# Converter.net
KiCad netlist of a schematic drawn in Altium Designer
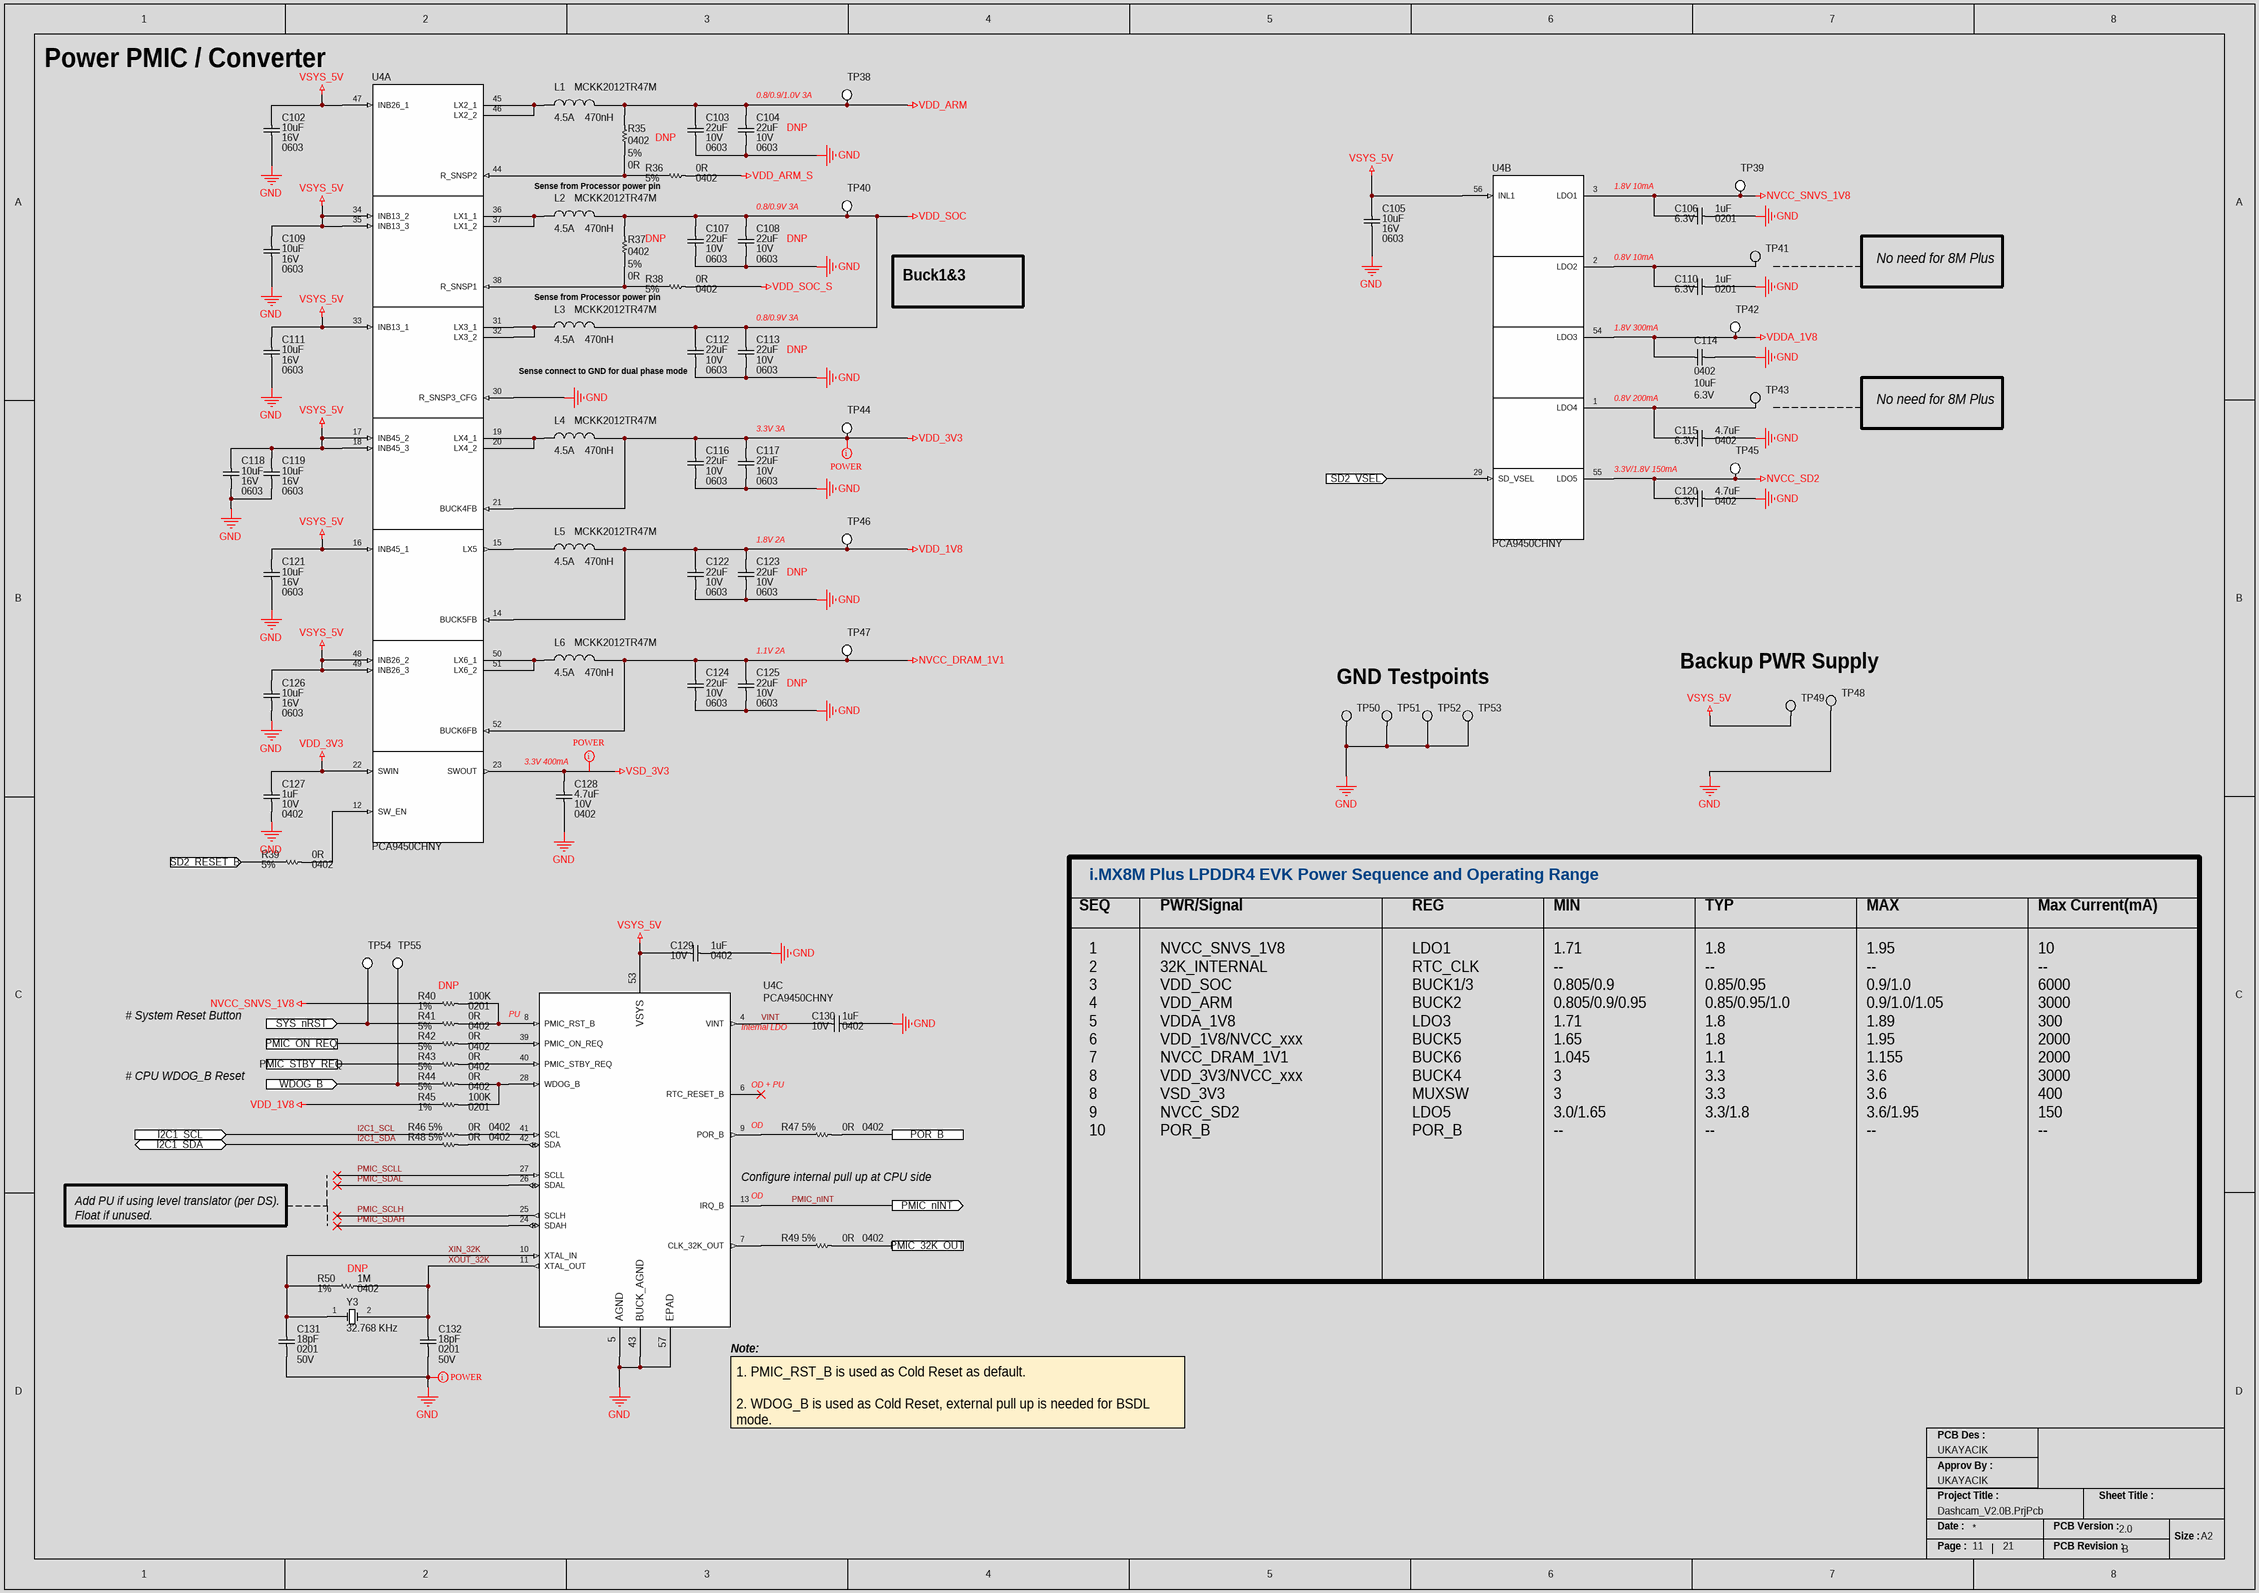
[diagram p0: Converter.SchDoc]

(export (version "E")
  (design (tool "Eeschema 10.0.6"))
  (components
    (comp (ref "C102")
      (value "GRM188R61C106MAALD")
      (footprint "CAP_0603_CAPC1608X08N")
      (description "0603 10 uF 16 V ±20% Tolerance X5R Multilayer Ceramic Chip Capacitor")
      (fields
        (field (name "MANUFACTURER") "Murata")
        (field (name "TOLERANCE") "20%")
        (field (name "VOLTAGE RATING") "16V")
        (field (name "CAPACITANCE") "10uF")
        (field (name "CASE/PACKAGE") "0603")
      )
      (libsource (lib "Electronic Devices_LIB") (part "CAP_10UF_16V_X5R_0603"))
    )
    (comp (ref "C103")
      (value "C1608X5R1A226M080AC")
      (footprint "CAP_0603_CAPC1608X08N")
      (description "Multilayer Ceramic Capacitor, 22 uF, 10 V, ± 20%, X5R, 0603 [1608 Metric]")
      (fields
        (field (name "MANUFACTURER") "TDK")
        (field (name "TOLERANCE") "20%")
        (field (name "CAPACITANCE") "22uF")
        (field (name "VOLTAGE RATING") "10V")
        (field (name "CASE CODE (IMPERIAL)") "0603")
      )
      (libsource (lib "Electronic Devices_LIB") (part "CAP_22UF_10V_X5R_0603"))
    )
    (comp (ref "C104")
      (value "C1608X5R1A226M080AC")
      (footprint "CAP_0603_CAPC1608X08N")
      (description "Multilayer Ceramic Capacitor, 22 uF, 10 V, ± 20%, X5R, 0603 [1608 Metric]")
      (fields
        (field (name "MANUFACTURER") "TDK")
        (field (name "TOLERANCE") "20%")
        (field (name "CAPACITANCE") "22uF")
        (field (name "VOLTAGE RATING") "10V")
        (field (name "CASE CODE (IMPERIAL)") "0603")
      )
      (libsource (lib "Electronic Devices_LIB") (part "CAP_22UF_10V_X5R_0603"))
    )
    (comp (ref "C105")
      (value "GRM188R61C106MAALD")
      (footprint "CAP_0603_CAPC1608X08N")
      (description "0603 10 uF 16 V ±20% Tolerance X5R Multilayer Ceramic Chip Capacitor")
      (fields
        (field (name "MANUFACTURER") "Murata")
        (field (name "TOLERANCE") "20%")
        (field (name "VOLTAGE RATING") "16V")
        (field (name "CAPACITANCE") "10uF")
        (field (name "CASE/PACKAGE") "0603")
      )
      (libsource (lib "Electronic Devices_LIB") (part "CAP_10UF_16V_X5R_0603"))
    )
    (comp (ref "C106")
      (value "02016D105MAT2A")
      (footprint "CAP_0201_CAPC0603X03N")
      (description "0201 1 uF 6.3 V ±20 % Tolerance X5R Surface Mount Multilayer Ceramic Capacitor")
      (fields
        (field (name "MANUFACTURER") "Kyocera AVX")
        (field (name "TOLERANCE") "20%")
        (field (name "VOLTAGE RATING (DC)") "6.3V")
        (field (name "CAPACITANCE") "1uF")
        (field (name "CASE/PACKAGE") "0201")
      )
      (libsource (lib "Electronic Devices_LIB") (part "CAP_1UF_6.3V_X5R_0201"))
    )
    (comp (ref "C107")
      (value "C1608X5R1A226M080AC")
      (footprint "CAP_0603_CAPC1608X08N")
      (description "Multilayer Ceramic Capacitor, 22 uF, 10 V, ± 20%, X5R, 0603 [1608 Metric]")
      (fields
        (field (name "MANUFACTURER") "TDK")
        (field (name "TOLERANCE") "20%")
        (field (name "CAPACITANCE") "22uF")
        (field (name "VOLTAGE RATING") "10V")
        (field (name "CASE CODE (IMPERIAL)") "0603")
      )
      (libsource (lib "Electronic Devices_LIB") (part "CAP_22UF_10V_X5R_0603"))
    )
    (comp (ref "C108")
      (value "C1608X5R1A226M080AC")
      (footprint "CAP_0603_CAPC1608X08N")
      (description "Multilayer Ceramic Capacitor, 22 uF, 10 V, ± 20%, X5R, 0603 [1608 Metric]")
      (fields
        (field (name "MANUFACTURER") "TDK")
        (field (name "TOLERANCE") "20%")
        (field (name "CAPACITANCE") "22uF")
        (field (name "VOLTAGE RATING") "10V")
        (field (name "CASE CODE (IMPERIAL)") "0603")
      )
      (libsource (lib "Electronic Devices_LIB") (part "CAP_22UF_10V_X5R_0603"))
    )
    (comp (ref "C109")
      (value "GRM188R61C106MAALD")
      (footprint "CAP_0603_CAPC1608X08N")
      (description "0603 10 uF 16 V ±20% Tolerance X5R Multilayer Ceramic Chip Capacitor")
      (fields
        (field (name "MANUFACTURER") "Murata")
        (field (name "TOLERANCE") "20%")
        (field (name "VOLTAGE RATING") "16V")
        (field (name "CAPACITANCE") "10uF")
        (field (name "CASE/PACKAGE") "0603")
      )
      (libsource (lib "Electronic Devices_LIB") (part "CAP_10UF_16V_X5R_0603"))
    )
    (comp (ref "C110")
      (value "02016D105MAT2A")
      (footprint "CAP_0201_CAPC0603X03N")
      (description "0201 1 uF 6.3 V ±20 % Tolerance X5R Surface Mount Multilayer Ceramic Capacitor")
      (fields
        (field (name "MANUFACTURER") "Kyocera AVX")
        (field (name "TOLERANCE") "20%")
        (field (name "VOLTAGE RATING (DC)") "6.3V")
        (field (name "CAPACITANCE") "1uF")
        (field (name "CASE/PACKAGE") "0201")
      )
      (libsource (lib "Electronic Devices_LIB") (part "CAP_1UF_6.3V_X5R_0201"))
    )
    (comp (ref "C111")
      (value "GRM188R61C106MAALD")
      (footprint "CAP_0603_CAPC1608X08N")
      (description "0603 10 uF 16 V ±20% Tolerance X5R Multilayer Ceramic Chip Capacitor")
      (fields
        (field (name "MANUFACTURER") "Murata")
        (field (name "TOLERANCE") "20%")
        (field (name "VOLTAGE RATING") "16V")
        (field (name "CAPACITANCE") "10uF")
        (field (name "CASE/PACKAGE") "0603")
      )
      (libsource (lib "Electronic Devices_LIB") (part "CAP_10UF_16V_X5R_0603"))
    )
    (comp (ref "C112")
      (value "C1608X5R1A226M080AC")
      (footprint "CAP_0603_CAPC1608X08N")
      (description "Multilayer Ceramic Capacitor, 22 uF, 10 V, ± 20%, X5R, 0603 [1608 Metric]")
      (fields
        (field (name "MANUFACTURER") "TDK")
        (field (name "TOLERANCE") "20%")
        (field (name "CAPACITANCE") "22uF")
        (field (name "VOLTAGE RATING") "10V")
        (field (name "CASE CODE (IMPERIAL)") "0603")
      )
      (libsource (lib "Electronic Devices_LIB") (part "CAP_22UF_10V_X5R_0603"))
    )
    (comp (ref "C113")
      (value "C1608X5R1A226M080AC")
      (footprint "CAP_0603_CAPC1608X08N")
      (description "Multilayer Ceramic Capacitor, 22 uF, 10 V, ± 20%, X5R, 0603 [1608 Metric]")
      (fields
        (field (name "MANUFACTURER") "TDK")
        (field (name "TOLERANCE") "20%")
        (field (name "CAPACITANCE") "22uF")
        (field (name "VOLTAGE RATING") "10V")
        (field (name "CASE CODE (IMPERIAL)") "0603")
      )
      (libsource (lib "Electronic Devices_LIB") (part "CAP_22UF_10V_X5R_0603"))
    )
    (comp (ref "C114")
      (value "CL05A106MQ5NUNC")
      (footprint "CAP_0402_CAPC1005X05N")
      (description "Cap Ceramic 10uF 6.3V X5R 20% SMD 0402 85C T/R")
      (fields
        (field (name "MANUFACTURER") "Samsung")
        (field (name "TOLERANCE") "20%")
        (field (name "CASE/PACKAGE") "0402")
        (field (name "CAPACITANCE") "10uF")
        (field (name "VOLTAGE RATING") "6.3V")
      )
      (libsource (lib "Electronic Devices_LIB") (part "CAP_10UF_6.3V_X5R_0402"))
    )
    (comp (ref "C115")
      (value "C1005X5R0J475M050BC")
      (footprint "CAP_0402_CAPC1005X05N")
      (description "Multilayer Ceramic Capacitor, 4.7 uF, 6.3 V, ± 20%, X5R, 0402 [1005 Metric]")
      (fields
        (field (name "MANUFACTURER") "TDK")
        (field (name "TOLERANCE") "20%")
        (field (name "CAPACITANCE") "4.7uF")
        (field (name "VOLTAGE RATING") "6.3V")
        (field (name "CASE/PACKAGE") "0402")
      )
      (libsource (lib "Electronic Devices_LIB") (part "CAP_4.7UF_6.3V_X5R_0402"))
    )
    (comp (ref "C116")
      (value "C1608X5R1A226M080AC")
      (footprint "CAP_0603_CAPC1608X08N")
      (description "Multilayer Ceramic Capacitor, 22 uF, 10 V, ± 20%, X5R, 0603 [1608 Metric]")
      (fields
        (field (name "MANUFACTURER") "TDK")
        (field (name "TOLERANCE") "20%")
        (field (name "CAPACITANCE") "22uF")
        (field (name "VOLTAGE RATING") "10V")
        (field (name "CASE CODE (IMPERIAL)") "0603")
      )
      (libsource (lib "Electronic Devices_LIB") (part "CAP_22UF_10V_X5R_0603"))
    )
    (comp (ref "C117")
      (value "C1608X5R1A226M080AC")
      (footprint "CAP_0603_CAPC1608X08N")
      (description "Multilayer Ceramic Capacitor, 22 uF, 10 V, ± 20%, X5R, 0603 [1608 Metric]")
      (fields
        (field (name "MANUFACTURER") "TDK")
        (field (name "TOLERANCE") "20%")
        (field (name "CAPACITANCE") "22uF")
        (field (name "VOLTAGE RATING") "10V")
        (field (name "CASE CODE (IMPERIAL)") "0603")
      )
      (libsource (lib "Electronic Devices_LIB") (part "CAP_22UF_10V_X5R_0603"))
    )
    (comp (ref "C118")
      (value "GRM188R61C106MAALD")
      (footprint "CAP_0603_CAPC1608X08N")
      (description "0603 10 uF 16 V ±20% Tolerance X5R Multilayer Ceramic Chip Capacitor")
      (fields
        (field (name "MANUFACTURER") "Murata")
        (field (name "TOLERANCE") "20%")
        (field (name "VOLTAGE RATING") "16V")
        (field (name "CAPACITANCE") "10uF")
        (field (name "CASE/PACKAGE") "0603")
      )
      (libsource (lib "Electronic Devices_LIB") (part "CAP_10UF_16V_X5R_0603"))
    )
    (comp (ref "C119")
      (value "GRM188R61C106MAALD")
      (footprint "CAP_0603_CAPC1608X08N")
      (description "0603 10 uF 16 V ±20% Tolerance X5R Multilayer Ceramic Chip Capacitor")
      (fields
        (field (name "MANUFACTURER") "Murata")
        (field (name "TOLERANCE") "20%")
        (field (name "VOLTAGE RATING") "16V")
        (field (name "CAPACITANCE") "10uF")
        (field (name "CASE/PACKAGE") "0603")
      )
      (libsource (lib "Electronic Devices_LIB") (part "CAP_10UF_16V_X5R_0603"))
    )
    (comp (ref "C120")
      (value "C1005X5R0J475M050BC")
      (footprint "CAP_0402_CAPC1005X05N")
      (description "Multilayer Ceramic Capacitor, 4.7 uF, 6.3 V, ± 20%, X5R, 0402 [1005 Metric]")
      (fields
        (field (name "MANUFACTURER") "TDK")
        (field (name "TOLERANCE") "20%")
        (field (name "CAPACITANCE") "4.7uF")
        (field (name "VOLTAGE RATING") "6.3V")
        (field (name "CASE/PACKAGE") "0402")
      )
      (libsource (lib "Electronic Devices_LIB") (part "CAP_4.7UF_6.3V_X5R_0402"))
    )
    (comp (ref "C121")
      (value "GRM188R61C106MAALD")
      (footprint "CAP_0603_CAPC1608X08N")
      (description "0603 10 uF 16 V ±20% Tolerance X5R Multilayer Ceramic Chip Capacitor")
      (fields
        (field (name "MANUFACTURER") "Murata")
        (field (name "TOLERANCE") "20%")
        (field (name "VOLTAGE RATING") "16V")
        (field (name "CAPACITANCE") "10uF")
        (field (name "CASE/PACKAGE") "0603")
      )
      (libsource (lib "Electronic Devices_LIB") (part "CAP_10UF_16V_X5R_0603"))
    )
    (comp (ref "C122")
      (value "C1608X5R1A226M080AC")
      (footprint "CAP_0603_CAPC1608X08N")
      (description "Multilayer Ceramic Capacitor, 22 uF, 10 V, ± 20%, X5R, 0603 [1608 Metric]")
      (fields
        (field (name "MANUFACTURER") "TDK")
        (field (name "TOLERANCE") "20%")
        (field (name "CAPACITANCE") "22uF")
        (field (name "VOLTAGE RATING") "10V")
        (field (name "CASE CODE (IMPERIAL)") "0603")
      )
      (libsource (lib "Electronic Devices_LIB") (part "CAP_22UF_10V_X5R_0603"))
    )
    (comp (ref "C123")
      (value "C1608X5R1A226M080AC")
      (footprint "CAP_0603_CAPC1608X08N")
      (description "Multilayer Ceramic Capacitor, 22 uF, 10 V, ± 20%, X5R, 0603 [1608 Metric]")
      (fields
        (field (name "MANUFACTURER") "TDK")
        (field (name "TOLERANCE") "20%")
        (field (name "CAPACITANCE") "22uF")
        (field (name "VOLTAGE RATING") "10V")
        (field (name "CASE CODE (IMPERIAL)") "0603")
      )
      (libsource (lib "Electronic Devices_LIB") (part "CAP_22UF_10V_X5R_0603"))
    )
    (comp (ref "C124")
      (value "C1608X5R1A226M080AC")
      (footprint "CAP_0603_CAPC1608X08N")
      (description "Multilayer Ceramic Capacitor, 22 uF, 10 V, ± 20%, X5R, 0603 [1608 Metric]")
      (fields
        (field (name "MANUFACTURER") "TDK")
        (field (name "TOLERANCE") "20%")
        (field (name "CAPACITANCE") "22uF")
        (field (name "VOLTAGE RATING") "10V")
        (field (name "CASE CODE (IMPERIAL)") "0603")
      )
      (libsource (lib "Electronic Devices_LIB") (part "CAP_22UF_10V_X5R_0603"))
    )
    (comp (ref "C125")
      (value "C1608X5R1A226M080AC")
      (footprint "CAP_0603_CAPC1608X08N")
      (description "Multilayer Ceramic Capacitor, 22 uF, 10 V, ± 20%, X5R, 0603 [1608 Metric]")
      (fields
        (field (name "MANUFACTURER") "TDK")
        (field (name "TOLERANCE") "20%")
        (field (name "CAPACITANCE") "22uF")
        (field (name "VOLTAGE RATING") "10V")
        (field (name "CASE CODE (IMPERIAL)") "0603")
      )
      (libsource (lib "Electronic Devices_LIB") (part "CAP_22UF_10V_X5R_0603"))
    )
    (comp (ref "C126")
      (value "GRM188R61C106MAALD")
      (footprint "CAP_0603_CAPC1608X08N")
      (description "0603 10 uF 16 V ±20% Tolerance X5R Multilayer Ceramic Chip Capacitor")
      (fields
        (field (name "MANUFACTURER") "Murata")
        (field (name "TOLERANCE") "20%")
        (field (name "VOLTAGE RATING") "16V")
        (field (name "CAPACITANCE") "10uF")
        (field (name "CASE/PACKAGE") "0603")
      )
      (libsource (lib "Electronic Devices_LIB") (part "CAP_10UF_16V_X5R_0603"))
    )
    (comp (ref "C127")
      (value "GRM155C81A105KA12D")
      (footprint "CAP_0402_CAPC1005X05N")
      (description "0402 10 V 1 uF ±10% Tolerance X6S Multilayer Ceramic Capacitor")
      (fields
        (field (name "MANUFACTURER") "Murata")
        (field (name "TOLERANCE") "10%")
        (field (name "VOLTAGE RATING") "10V")
        (field (name "CAPACITANCE") "1uF")
        (field (name "CASE/PACKAGE") "0402")
      )
      (libsource (lib "Electronic Devices_LIB") (part "CAP_1UF_10V_X6S_0402"))
    )
    (comp (ref "C128")
      (value "CL05A475KP5NRNC")
      (footprint "CAP_0402_CAPC1005X05N")
      (description "Multilayer Ceramic Capacitor, 4.7 uF, 10 V, ± 10%, X5R, 0402 [1005 Metric]")
      (fields
        (field (name "MANUFACTURER") "Samsung")
        (field (name "TOLERANCE") "10%")
        (field (name "CAPACITANCE") "4.7uF")
        (field (name "VOLTAGE RATING") "10V")
        (field (name "CASE/PACKAGE") "0402")
      )
      (libsource (lib "Electronic Devices_LIB") (part "CAP_4.7UF_10V_X5R_0402"))
    )
    (comp (ref "C129")
      (value "GRM155C81A105KA12D")
      (footprint "CAP_0402_CAPC1005X05N")
      (description "0402 10 V 1 uF ±10% Tolerance X6S Multilayer Ceramic Capacitor")
      (fields
        (field (name "MANUFACTURER") "Murata")
        (field (name "TOLERANCE") "10%")
        (field (name "VOLTAGE RATING") "10V")
        (field (name "CAPACITANCE") "1uF")
        (field (name "CASE/PACKAGE") "0402")
      )
      (libsource (lib "Electronic Devices_LIB") (part "CAP_1UF_10V_X6S_0402"))
    )
    (comp (ref "C130")
      (value "GRM155C81A105KA12D")
      (footprint "CAP_0402_CAPC1005X05N")
      (description "0402 10 V 1 uF ±10% Tolerance X6S Multilayer Ceramic Capacitor")
      (fields
        (field (name "MANUFACTURER") "Murata")
        (field (name "TOLERANCE") "10%")
        (field (name "VOLTAGE RATING") "10V")
        (field (name "CAPACITANCE") "1uF")
        (field (name "CASE/PACKAGE") "0402")
      )
      (libsource (lib "Electronic Devices_LIB") (part "CAP_1UF_10V_X6S_0402"))
    )
    (comp (ref "C131")
      (value "GRM0335C1H180JA01D")
      (footprint "CAP_0201_CAPC0603X03N")
      (description "Multilayer Ceramic Capacitor, 18 pF, 50 V, ± 5%, C0G (NP0), 0201 [0603 Metric]")
      (fields
        (field (name "MANUFACTURER") "Murata")
        (field (name "TOLERANCE") "5%")
        (field (name "CAPACITANCE") "18pF")
        (field (name "VOLTAGE RATING") "50V")
        (field (name "CASE/PACKAGE") "0201")
      )
      (libsource (lib "Electronic Devices_LIB") (part "CAP_18PF_50V_NP0_0201"))
    )
    (comp (ref "C132")
      (value "GRM0335C1H180JA01D")
      (footprint "CAP_0201_CAPC0603X03N")
      (description "Multilayer Ceramic Capacitor, 18 pF, 50 V, ± 5%, C0G (NP0), 0201 [0603 Metric]")
      (fields
        (field (name "MANUFACTURER") "Murata")
        (field (name "TOLERANCE") "5%")
        (field (name "CAPACITANCE") "18pF")
        (field (name "VOLTAGE RATING") "50V")
        (field (name "CASE/PACKAGE") "0201")
      )
      (libsource (lib "Electronic Devices_LIB") (part "CAP_18PF_50V_NP0_0201"))
    )
    (comp (ref "L1")
      (value "MCKK2012TR47M")
      (footprint "IND_0805_INDC2012X10N")
      (description "Inductor Power Chip Multi-Layer 0.47uH 20% 1MHz Metal 3.1A 0.039Ohm DCR 0805 T/R")
      (fields
        (field (name "MANUFACTURER") "Taiyo Yuden")
        (field (name "TOLERANCE") "20%")
        (field (name "CURRENT RATING") "4.5A")
        (field (name "INDUCTANCE") "470nH")
      )
      (libsource (lib "Electronic Devices_LIB") (part "IND_0.47uH_4.5A_MCKK2012TR47M"))
    )
    (comp (ref "L2")
      (value "MCKK2012TR47M")
      (footprint "IND_0805_INDC2012X10N")
      (description "Inductor Power Chip Multi-Layer 0.47uH 20% 1MHz Metal 3.1A 0.039Ohm DCR 0805 T/R")
      (fields
        (field (name "MANUFACTURER") "Taiyo Yuden")
        (field (name "TOLERANCE") "20%")
        (field (name "CURRENT RATING") "4.5A")
        (field (name "INDUCTANCE") "470nH")
      )
      (libsource (lib "Electronic Devices_LIB") (part "IND_0.47uH_4.5A_MCKK2012TR47M"))
    )
    (comp (ref "L3")
      (value "MCKK2012TR47M")
      (footprint "IND_0805_INDC2012X10N")
      (description "Inductor Power Chip Multi-Layer 0.47uH 20% 1MHz Metal 3.1A 0.039Ohm DCR 0805 T/R")
      (fields
        (field (name "MANUFACTURER") "Taiyo Yuden")
        (field (name "TOLERANCE") "20%")
        (field (name "CURRENT RATING") "4.5A")
        (field (name "INDUCTANCE") "470nH")
      )
      (libsource (lib "Electronic Devices_LIB") (part "IND_0.47uH_4.5A_MCKK2012TR47M"))
    )
    (comp (ref "L4")
      (value "MCKK2012TR47M")
      (footprint "IND_0805_INDC2012X10N")
      (description "Inductor Power Chip Multi-Layer 0.47uH 20% 1MHz Metal 3.1A 0.039Ohm DCR 0805 T/R")
      (fields
        (field (name "MANUFACTURER") "Taiyo Yuden")
        (field (name "TOLERANCE") "20%")
        (field (name "CURRENT RATING") "4.5A")
        (field (name "INDUCTANCE") "470nH")
      )
      (libsource (lib "Electronic Devices_LIB") (part "IND_0.47uH_4.5A_MCKK2012TR47M"))
    )
    (comp (ref "L5")
      (value "MCKK2012TR47M")
      (footprint "IND_0805_INDC2012X10N")
      (description "Inductor Power Chip Multi-Layer 0.47uH 20% 1MHz Metal 3.1A 0.039Ohm DCR 0805 T/R")
      (fields
        (field (name "MANUFACTURER") "Taiyo Yuden")
        (field (name "TOLERANCE") "20%")
        (field (name "CURRENT RATING") "4.5A")
        (field (name "INDUCTANCE") "470nH")
      )
      (libsource (lib "Electronic Devices_LIB") (part "IND_0.47uH_4.5A_MCKK2012TR47M"))
    )
    (comp (ref "L6")
      (value "MCKK2012TR47M")
      (footprint "IND_0805_INDC2012X10N")
      (description "Inductor Power Chip Multi-Layer 0.47uH 20% 1MHz Metal 3.1A 0.039Ohm DCR 0805 T/R")
      (fields
        (field (name "MANUFACTURER") "Taiyo Yuden")
        (field (name "TOLERANCE") "20%")
        (field (name "CURRENT RATING") "4.5A")
        (field (name "INDUCTANCE") "470nH")
      )
      (libsource (lib "Electronic Devices_LIB") (part "IND_0.47uH_4.5A_MCKK2012TR47M"))
    )
    (comp (ref "R35")
      (value "ERJ-2GE0R00X")
      (footprint "RES_0402_RESC1005X04N")
      (description "SMD Chip Resistor, Jumper, 0 ohm, 100 mW, 0402 [1005 Metric], Thick Film, General Purpose")
      (fields
        (field (name "MANUFACTURER") "Panasonic")
        (field (name "CASE CODE (IMPERIAL)") "0402")
        (field (name "TOLERANCE") "5%")
        (field (name "RESISTANCE") "0R")
      )
      (libsource (lib "Electronic Devices_LIB") (part "RES_0R_5%_100mW_0402"))
    )
    (comp (ref "R36")
      (value "ERJ-2GE0R00X")
      (footprint "RES_0402_RESC1005X04N")
      (description "SMD Chip Resistor, Jumper, 0 ohm, 100 mW, 0402 [1005 Metric], Thick Film, General Purpose")
      (fields
        (field (name "MANUFACTURER") "Panasonic")
        (field (name "CASE CODE (IMPERIAL)") "0402")
        (field (name "TOLERANCE") "5%")
        (field (name "RESISTANCE") "0R")
      )
      (libsource (lib "Electronic Devices_LIB") (part "RES_0R_5%_100mW_0402"))
    )
    (comp (ref "R37")
      (value "ERJ-2GE0R00X")
      (footprint "RES_0402_RESC1005X04N")
      (description "SMD Chip Resistor, Jumper, 0 ohm, 100 mW, 0402 [1005 Metric], Thick Film, General Purpose")
      (fields
        (field (name "MANUFACTURER") "Panasonic")
        (field (name "CASE CODE (IMPERIAL)") "0402")
        (field (name "TOLERANCE") "5%")
        (field (name "RESISTANCE") "0R")
      )
      (libsource (lib "Electronic Devices_LIB") (part "RES_0R_5%_100mW_0402"))
    )
    (comp (ref "R38")
      (value "ERJ-2GE0R00X")
      (footprint "RES_0402_RESC1005X04N")
      (description "SMD Chip Resistor, Jumper, 0 ohm, 100 mW, 0402 [1005 Metric], Thick Film, General Purpose")
      (fields
        (field (name "MANUFACTURER") "Panasonic")
        (field (name "CASE CODE (IMPERIAL)") "0402")
        (field (name "TOLERANCE") "5%")
        (field (name "RESISTANCE") "0R")
      )
      (libsource (lib "Electronic Devices_LIB") (part "RES_0R_5%_100mW_0402"))
    )
    (comp (ref "R39")
      (value "ERJ-2GE0R00X")
      (footprint "RES_0402_RESC1005X04N")
      (description "SMD Chip Resistor, Jumper, 0 ohm, 100 mW, 0402 [1005 Metric], Thick Film, General Purpose")
      (fields
        (field (name "MANUFACTURER") "Panasonic")
        (field (name "CASE CODE (IMPERIAL)") "0402")
        (field (name "TOLERANCE") "5%")
        (field (name "RESISTANCE") "0R")
      )
      (libsource (lib "Electronic Devices_LIB") (part "RES_0R_5%_100mW_0402"))
    )
    (comp (ref "R40")
      (value "RC0201FR-07100KL")
      (footprint "RES_0201_RESC0603X02N")
      (description "SMD Chip Resistor, 100 kOhm, ± 1%, 50 mW, 0201 [0603 Metric], Thick Film, General Purpose")
      (fields
        (field (name "MANUFACTURER") "Yageo")
        (field (name "RESISTANCE") "100K")
        (field (name "TOLERANCE") "1%")
        (field (name "CASE/PACKAGE") "0201")
      )
      (libsource (lib "Electronic Devices_LIB") (part "RES_100K_1%_50mW_0201"))
    )
    (comp (ref "R41")
      (value "ERJ-2GE0R00X")
      (footprint "RES_0402_RESC1005X04N")
      (description "SMD Chip Resistor, Jumper, 0 ohm, 100 mW, 0402 [1005 Metric], Thick Film, General Purpose")
      (fields
        (field (name "MANUFACTURER") "Panasonic")
        (field (name "CASE CODE (IMPERIAL)") "0402")
        (field (name "TOLERANCE") "5%")
        (field (name "RESISTANCE") "0R")
      )
      (libsource (lib "Electronic Devices_LIB") (part "RES_0R_5%_100mW_0402"))
    )
    (comp (ref "R42")
      (value "ERJ-2GE0R00X")
      (footprint "RES_0402_RESC1005X04N")
      (description "SMD Chip Resistor, Jumper, 0 ohm, 100 mW, 0402 [1005 Metric], Thick Film, General Purpose")
      (fields
        (field (name "MANUFACTURER") "Panasonic")
        (field (name "CASE CODE (IMPERIAL)") "0402")
        (field (name "TOLERANCE") "5%")
        (field (name "RESISTANCE") "0R")
      )
      (libsource (lib "Electronic Devices_LIB") (part "RES_0R_5%_100mW_0402"))
    )
    (comp (ref "R43")
      (value "ERJ-2GE0R00X")
      (footprint "RES_0402_RESC1005X04N")
      (description "SMD Chip Resistor, Jumper, 0 ohm, 100 mW, 0402 [1005 Metric], Thick Film, General Purpose")
      (fields
        (field (name "MANUFACTURER") "Panasonic")
        (field (name "CASE CODE (IMPERIAL)") "0402")
        (field (name "TOLERANCE") "5%")
        (field (name "RESISTANCE") "0R")
      )
      (libsource (lib "Electronic Devices_LIB") (part "RES_0R_5%_100mW_0402"))
    )
    (comp (ref "R44")
      (value "ERJ-2GE0R00X")
      (footprint "RES_0402_RESC1005X04N")
      (description "SMD Chip Resistor, Jumper, 0 ohm, 100 mW, 0402 [1005 Metric], Thick Film, General Purpose")
      (fields
        (field (name "MANUFACTURER") "Panasonic")
        (field (name "CASE CODE (IMPERIAL)") "0402")
        (field (name "TOLERANCE") "5%")
        (field (name "RESISTANCE") "0R")
      )
      (libsource (lib "Electronic Devices_LIB") (part "RES_0R_5%_100mW_0402"))
    )
    (comp (ref "R45")
      (value "RC0201FR-07100KL")
      (footprint "RES_0201_RESC0603X02N")
      (description "SMD Chip Resistor, 100 kOhm, ± 1%, 50 mW, 0201 [0603 Metric], Thick Film, General Purpose")
      (fields
        (field (name "MANUFACTURER") "Yageo")
        (field (name "RESISTANCE") "100K")
        (field (name "TOLERANCE") "1%")
        (field (name "CASE/PACKAGE") "0201")
      )
      (libsource (lib "Electronic Devices_LIB") (part "RES_100K_1%_50mW_0201"))
    )
    (comp (ref "R46")
      (value "ERJ-2GE0R00X")
      (footprint "RES_0402_RESC1005X04N")
      (description "SMD Chip Resistor, Jumper, 0 ohm, 100 mW, 0402 [1005 Metric], Thick Film, General Purpose")
      (fields
        (field (name "MANUFACTURER") "Panasonic")
        (field (name "CASE CODE (IMPERIAL)") "0402")
        (field (name "TOLERANCE") "5%")
        (field (name "RESISTANCE") "0R")
      )
      (libsource (lib "Electronic Devices_LIB") (part "RES_0R_5%_100mW_0402"))
    )
    (comp (ref "R47")
      (value "ERJ-2GE0R00X")
      (footprint "RES_0402_RESC1005X04N")
      (description "SMD Chip Resistor, Jumper, 0 ohm, 100 mW, 0402 [1005 Metric], Thick Film, General Purpose")
      (fields
        (field (name "MANUFACTURER") "Panasonic")
        (field (name "CASE CODE (IMPERIAL)") "0402")
        (field (name "TOLERANCE") "5%")
        (field (name "RESISTANCE") "0R")
      )
      (libsource (lib "Electronic Devices_LIB") (part "RES_0R_5%_100mW_0402"))
    )
    (comp (ref "R48")
      (value "ERJ-2GE0R00X")
      (footprint "RES_0402_RESC1005X04N")
      (description "SMD Chip Resistor, Jumper, 0 ohm, 100 mW, 0402 [1005 Metric], Thick Film, General Purpose")
      (fields
        (field (name "MANUFACTURER") "Panasonic")
        (field (name "CASE CODE (IMPERIAL)") "0402")
        (field (name "TOLERANCE") "5%")
        (field (name "RESISTANCE") "0R")
      )
      (libsource (lib "Electronic Devices_LIB") (part "RES_0R_5%_100mW_0402"))
    )
    (comp (ref "R49")
      (value "ERJ-2GE0R00X")
      (footprint "RES_0402_RESC1005X04N")
      (description "SMD Chip Resistor, Jumper, 0 ohm, 100 mW, 0402 [1005 Metric], Thick Film, General Purpose")
      (fields
        (field (name "MANUFACTURER") "Panasonic")
        (field (name "CASE CODE (IMPERIAL)") "0402")
        (field (name "TOLERANCE") "5%")
        (field (name "RESISTANCE") "0R")
      )
      (libsource (lib "Electronic Devices_LIB") (part "RES_0R_5%_100mW_0402"))
    )
    (comp (ref "R50")
      (value "CR0402-FX-1004GLF")
      (footprint "RES_0402_RESC1005X04N")
      (description "Res Thick Film 0402 1M Ohm 1% 1/16W ±100ppm/°C Molded SMD SMD Paper Tape on Plastic Reel")
      (fields
        (field (name "MANUFACTURER") "Bourns")
        (field (name "RESISTANCE") "1M")
        (field (name "TOLERANCE") "1%")
        (field (name "CASE/PACKAGE") "0402")
      )
      (libsource (lib "Electronic Devices_LIB") (part "RES_1M_1%_63mW_0402"))
    )
    (comp (ref "TP38")
      (value "NO COMPONENT")
      (footprint "TP_PAD_0.8MM_SMD_ROUND")
      (description "Test Point, SMD pad, round, 1.5mm, 1.6mm, 3mm diameter")
      (libsource (lib "Electronic Devices_LIB") (part "TP_PAD_SMD_Round"))
    )
    (comp (ref "TP39")
      (value "NO COMPONENT")
      (footprint "TP_PAD_0.8MM_SMD_ROUND")
      (description "Test Point, SMD pad, round, 1.5mm, 1.6mm, 3mm diameter")
      (libsource (lib "Electronic Devices_LIB") (part "TP_PAD_SMD_Round"))
    )
    (comp (ref "TP40")
      (value "NO COMPONENT")
      (footprint "TP_PAD_0.8MM_SMD_ROUND")
      (description "Test Point, SMD pad, round, 1.5mm, 1.6mm, 3mm diameter")
      (libsource (lib "Electronic Devices_LIB") (part "TP_PAD_SMD_Round"))
    )
    (comp (ref "TP41")
      (value "NO COMPONENT")
      (footprint "TP_PAD_0.5MM_SMD_ROUND")
      (description "Test Point, SMD pad, round, 1.5mm, 1.6mm, 3mm diameter")
      (libsource (lib "Electronic Devices_LIB") (part "TP_PAD_SMD_SMALL"))
    )
    (comp (ref "TP42")
      (value "NO COMPONENT")
      (footprint "TP_PAD_0.8MM_SMD_ROUND")
      (description "Test Point, SMD pad, round, 1.5mm, 1.6mm, 3mm diameter")
      (libsource (lib "Electronic Devices_LIB") (part "TP_PAD_SMD_Round"))
    )
    (comp (ref "TP43")
      (value "NO COMPONENT")
      (footprint "TP_PAD_0.5MM_SMD_ROUND")
      (description "Test Point, SMD pad, round, 1.5mm, 1.6mm, 3mm diameter")
      (libsource (lib "Electronic Devices_LIB") (part "TP_PAD_SMD_SMALL"))
    )
    (comp (ref "TP44")
      (value "NO COMPONENT")
      (footprint "TP_PAD_0.8MM_SMD_ROUND")
      (description "Test Point, SMD pad, round, 1.5mm, 1.6mm, 3mm diameter")
      (libsource (lib "Electronic Devices_LIB") (part "TP_PAD_SMD_Round"))
    )
    (comp (ref "TP45")
      (value "NO COMPONENT")
      (footprint "TP_PAD_0.8MM_SMD_ROUND")
      (description "Test Point, SMD pad, round, 1.5mm, 1.6mm, 3mm diameter")
      (libsource (lib "Electronic Devices_LIB") (part "TP_PAD_SMD_Round"))
    )
    (comp (ref "TP46")
      (value "NO COMPONENT")
      (footprint "TP_PAD_0.8MM_SMD_ROUND")
      (description "Test Point, SMD pad, round, 1.5mm, 1.6mm, 3mm diameter")
      (libsource (lib "Electronic Devices_LIB") (part "TP_PAD_SMD_Round"))
    )
    (comp (ref "TP47")
      (value "NO COMPONENT")
      (footprint "TP_PAD_0.8MM_SMD_ROUND")
      (description "Test Point, SMD pad, round, 1.5mm, 1.6mm, 3mm diameter")
      (libsource (lib "Electronic Devices_LIB") (part "TP_PAD_SMD_Round"))
    )
    (comp (ref "TP48")
      (value "NO COMPONENT")
      (footprint "TP_PAD_0.5MM_SMD_ROUND")
      (description "Test Point, SMD pad, round, 1.5mm, 1.6mm, 3mm diameter")
      (libsource (lib "Electronic Devices_LIB") (part "TP_PAD_SMD_SMALL"))
    )
    (comp (ref "TP49")
      (value "NO COMPONENT")
      (footprint "TP_PAD_0.5MM_SMD_ROUND")
      (description "Test Point, SMD pad, round, 1.5mm, 1.6mm, 3mm diameter")
      (libsource (lib "Electronic Devices_LIB") (part "TP_PAD_SMD_SMALL"))
    )
    (comp (ref "TP50")
      (value "NO COMPONENT")
      (footprint "TP_PAD_0.5MM_SMD_ROUND")
      (description "Test Point, SMD pad, round, 1.5mm, 1.6mm, 3mm diameter")
      (libsource (lib "Electronic Devices_LIB") (part "TP_PAD_SMD_SMALL"))
    )
    (comp (ref "TP51")
      (value "NO COMPONENT")
      (footprint "TP_PAD_0.5MM_SMD_ROUND")
      (description "Test Point, SMD pad, round, 1.5mm, 1.6mm, 3mm diameter")
      (libsource (lib "Electronic Devices_LIB") (part "TP_PAD_SMD_SMALL"))
    )
    (comp (ref "TP52")
      (value "NO COMPONENT")
      (footprint "TP_PAD_0.5MM_SMD_ROUND")
      (description "Test Point, SMD pad, round, 1.5mm, 1.6mm, 3mm diameter")
      (libsource (lib "Electronic Devices_LIB") (part "TP_PAD_SMD_SMALL"))
    )
    (comp (ref "TP53")
      (value "NO COMPONENT")
      (footprint "TP_PAD_0.5MM_SMD_ROUND")
      (description "Test Point, SMD pad, round, 1.5mm, 1.6mm, 3mm diameter")
      (libsource (lib "Electronic Devices_LIB") (part "TP_PAD_SMD_SMALL"))
    )
    (comp (ref "TP54")
      (value "NO COMPONENT")
      (footprint "TP_PAD_0.8MM_SMD_ROUND")
      (description "Test Point, SMD pad, round, 1.5mm, 1.6mm, 3mm diameter")
      (libsource (lib "Electronic Devices_LIB") (part "TP_PAD_SMD_Round"))
    )
    (comp (ref "TP55")
      (value "NO COMPONENT")
      (footprint "TP_PAD_0.8MM_SMD_ROUND")
      (description "Test Point, SMD pad, round, 1.5mm, 1.6mm, 3mm diameter")
      (libsource (lib "Electronic Devices_LIB") (part "TP_PAD_SMD_Round"))
    )
    (comp (ref "U4")
      (value "PCA9450CHNY")
      (footprint "IC_PMIC_QFN40P800X800X100-57N-D")
      (description "SAMPLE FPN ONLY - Power Management Specialized - PMIC PMIC for i.MX8M Plus(865S)")
      (fields (field (name "MANUFACTURER") "NXP Semiconductors"))
      (libsource (lib "Electronic Devices_LIB") (part "IC_PMIC_8MPLUS_PCA9450CHNY"))
    )
    (comp (ref "Y3")
      (value "ABS07-32.768KHZ-T")
      (footprint "CRYSTAL_ABS07-32.768KHZ-T")
      (description "Crystal 0.032768MHz ±20ppm (Tol) 12.5pF Flexural 70000Ohm 2-Pin CSMD T/R")
      (fields
        (field (name "MANUFACTURER") "Abracon")
        (field (name "TOLERANCE") "20ppm")
        (field (name "OPERATING FREQUENCY") "32.768 KHz")
      )
      (libsource (lib "Electronic Devices_LIB") (part "CRYSTAL_ABRACON_32.768KHz_ABS07-32.768KHZ-T"))
    )
  )
  (nets
    (net (code "1") (name "/I2C1_SCL") (class "Default")
      (node (ref "R46") (pin "1") (pinfunction "1_1") (pintype "passive"))
    )
    (net (code "2") (name "/I2C1_SDA") (class "Default")
      (node (ref "R48") (pin "1") (pinfunction "1_1") (pintype "passive"))
    )
    (net (code "3") (name "/PMIC_32K_OUT") (class "Default")
      (node (ref "R49") (pin "2") (pinfunction "2_2") (pintype "passive"))
    )
    (net (code "4") (name "/PMIC_ON_REQ") (class "Default")
      (node (ref "R42") (pin "1") (pinfunction "1_1") (pintype "passive"))
    )
    (net (code "5") (name "/PMIC_SCLH") (class "Default")
      (node (ref "U4") (pin "25") (pinfunction "SCLH_25") (pintype "output+no_connect"))
    )
    (net (code "6") (name "/PMIC_SCLL") (class "Default")
      (node (ref "U4") (pin "27") (pinfunction "SCLL_27") (pintype "input+no_connect"))
    )
    (net (code "7") (name "/PMIC_SDAH") (class "Default")
      (node (ref "U4") (pin "24") (pinfunction "SDAH_24") (pintype "bidirectional+no_connect"))
    )
    (net (code "8") (name "/PMIC_SDAL") (class "Default")
      (node (ref "U4") (pin "26") (pinfunction "SDAL_26") (pintype "bidirectional+no_connect"))
    )
    (net (code "9") (name "/PMIC_STBY_REQ") (class "Default")
      (node (ref "R43") (pin "1") (pinfunction "1_1") (pintype "passive"))
    )
    (net (code "10") (name "/PMIC_nINT") (class "Default")
      (node (ref "U4") (pin "13") (pinfunction "IRQ_B_13") (pintype "open_collector"))
    )
    (net (code "11") (name "/POR_B") (class "Default")
      (node (ref "R47") (pin "2") (pinfunction "2_2") (pintype "passive"))
    )
    (net (code "12") (name "/SD2_RESET_B") (class "Default")
      (node (ref "R39") (pin "1") (pinfunction "1_1") (pintype "passive"))
    )
    (net (code "13") (name "/SD2_VSEL") (class "Default")
      (node (ref "U4") (pin "29") (pinfunction "SD_VSEL_29") (pintype "input"))
    )
    (net (code "14") (name "/SYS_nRST") (class "Default")
      (node (ref "R41") (pin "1") (pinfunction "1_1") (pintype "passive"))
      (node (ref "TP54") (pin "1") (pinfunction "1_1") (pintype "passive"))
    )
    (net (code "15") (name "/VINT") (class "Default")
      (node (ref "C130") (pin "2") (pinfunction "2_2") (pintype "passive"))
      (node (ref "U4") (pin "4") (pinfunction "VINT_4") (pintype "output"))
    )
    (net (code "16") (name "/WDOG_B") (class "Default")
      (node (ref "R44") (pin "1") (pinfunction "1_1") (pintype "passive"))
      (node (ref "TP55") (pin "1") (pinfunction "1_1") (pintype "passive"))
    )
    (net (code "17") (name "/XIN_32K") (class "Default")
      (node (ref "C131") (pin "2") (pinfunction "2_2") (pintype "passive"))
      (node (ref "R50") (pin "1") (pinfunction "1_1") (pintype "passive"))
      (node (ref "U4") (pin "10") (pinfunction "XTAL_IN_10") (pintype "input"))
      (node (ref "Y3") (pin "1") (pinfunction "OSC1_1") (pintype "passive"))
    )
    (net (code "18") (name "/XOUT_32K") (class "Default")
      (node (ref "C132") (pin "2") (pinfunction "2_2") (pintype "passive"))
      (node (ref "R50") (pin "2") (pinfunction "2_2") (pintype "passive"))
      (node (ref "U4") (pin "11") (pinfunction "XTAL_OUT_11") (pintype "output"))
      (node (ref "Y3") (pin "2") (pinfunction "OSC2_2") (pintype "passive"))
    )
    (net (code "19") (name "GND") (class "Default")
      (node (ref "C102") (pin "1") (pinfunction "1_1") (pintype "passive"))
      (node (ref "C103") (pin "1") (pinfunction "1_1") (pintype "passive"))
      (node (ref "C104") (pin "1") (pinfunction "1_1") (pintype "passive"))
      (node (ref "C105") (pin "1") (pinfunction "1_1") (pintype "passive"))
      (node (ref "C106") (pin "2") (pinfunction "2_2") (pintype "passive"))
      (node (ref "C107") (pin "1") (pinfunction "1_1") (pintype "passive"))
      (node (ref "C108") (pin "1") (pinfunction "1_1") (pintype "passive"))
      (node (ref "C109") (pin "1") (pinfunction "1_1") (pintype "passive"))
      (node (ref "C110") (pin "2") (pinfunction "2_2") (pintype "passive"))
      (node (ref "C111") (pin "1") (pinfunction "1_1") (pintype "passive"))
      (node (ref "C112") (pin "1") (pinfunction "1_1") (pintype "passive"))
      (node (ref "C113") (pin "1") (pinfunction "1_1") (pintype "passive"))
      (node (ref "C114") (pin "1") (pinfunction "1_1") (pintype "passive"))
      (node (ref "C115") (pin "2") (pinfunction "2_2") (pintype "passive"))
      (node (ref "C116") (pin "1") (pinfunction "1_1") (pintype "passive"))
      (node (ref "C117") (pin "1") (pinfunction "1_1") (pintype "passive"))
      (node (ref "C118") (pin "1") (pinfunction "1_1") (pintype "passive"))
      (node (ref "C119") (pin "1") (pinfunction "1_1") (pintype "passive"))
      (node (ref "C120") (pin "2") (pinfunction "2_2") (pintype "passive"))
      (node (ref "C121") (pin "1") (pinfunction "1_1") (pintype "passive"))
      (node (ref "C122") (pin "1") (pinfunction "1_1") (pintype "passive"))
      (node (ref "C123") (pin "1") (pinfunction "1_1") (pintype "passive"))
      (node (ref "C124") (pin "1") (pinfunction "1_1") (pintype "passive"))
      (node (ref "C125") (pin "1") (pinfunction "1_1") (pintype "passive"))
      (node (ref "C126") (pin "1") (pinfunction "1_1") (pintype "passive"))
      (node (ref "C127") (pin "1") (pinfunction "1_1") (pintype "passive"))
      (node (ref "C128") (pin "1") (pinfunction "1_1") (pintype "passive"))
      (node (ref "C129") (pin "1") (pinfunction "1_1") (pintype "passive"))
      (node (ref "C130") (pin "1") (pinfunction "1_1") (pintype "passive"))
      (node (ref "C131") (pin "1") (pinfunction "1_1") (pintype "passive"))
      (node (ref "C132") (pin "1") (pinfunction "1_1") (pintype "passive"))
      (node (ref "TP48") (pin "1") (pinfunction "1_1") (pintype "passive"))
      (node (ref "TP50") (pin "1") (pinfunction "1_1") (pintype "passive"))
      (node (ref "TP51") (pin "1") (pinfunction "1_1") (pintype "passive"))
      (node (ref "TP52") (pin "1") (pinfunction "1_1") (pintype "passive"))
      (node (ref "TP53") (pin "1") (pinfunction "1_1") (pintype "passive"))
      (node (ref "U4") (pin "30") (pinfunction "R_SNSP3_CFG_30") (pintype "input"))
      (node (ref "U4") (pin "43") (pinfunction "BUCK_AGND_43") (pintype "power_in"))
      (node (ref "U4") (pin "5") (pinfunction "AGND_5") (pintype "power_in"))
      (node (ref "U4") (pin "57") (pinfunction "EPAD_57") (pintype "power_in"))
    )
    (net (code "20") (name "NVCC_DRAM_1V1") (class "Default")
      (node (ref "C124") (pin "2") (pinfunction "2_2") (pintype "passive"))
      (node (ref "C125") (pin "2") (pinfunction "2_2") (pintype "passive"))
      (node (ref "L6") (pin "2") (pinfunction "2_2") (pintype "passive"))
      (node (ref "TP47") (pin "1") (pinfunction "1_1") (pintype "passive"))
      (node (ref "U4") (pin "52") (pinfunction "BUCK6FB_52") (pintype "input"))
    )
    (net (code "21") (name "NVCC_SD2") (class "Default")
      (node (ref "C120") (pin "1") (pinfunction "1_1") (pintype "passive"))
      (node (ref "TP45") (pin "1") (pinfunction "1_1") (pintype "passive"))
      (node (ref "U4") (pin "55") (pinfunction "LDO5_55") (pintype "passive"))
    )
    (net (code "22") (name "NVCC_SNVS_1V8") (class "Default")
      (node (ref "C106") (pin "1") (pinfunction "1_1") (pintype "passive"))
      (node (ref "R40") (pin "1") (pinfunction "1_1") (pintype "passive"))
      (node (ref "TP39") (pin "1") (pinfunction "1_1") (pintype "passive"))
      (node (ref "U4") (pin "3") (pinfunction "LDO1_3") (pintype "passive"))
    )
    (net (code "23") (name "Net-(U4A-LX1_1)") (class "Default")
      (node (ref "L2") (pin "1") (pinfunction "1_1") (pintype "passive"))
      (node (ref "U4") (pin "36") (pinfunction "LX1_1_36") (pintype "passive"))
      (node (ref "U4") (pin "37") (pinfunction "LX1_2_37") (pintype "passive"))
    )
    (net (code "24") (name "Net-(U4A-LX2_1)") (class "Default")
      (node (ref "L1") (pin "1") (pinfunction "1_1") (pintype "passive"))
      (node (ref "U4") (pin "45") (pinfunction "LX2_1_45") (pintype "passive"))
      (node (ref "U4") (pin "46") (pinfunction "LX2_2_46") (pintype "passive"))
    )
    (net (code "25") (name "Net-(U4A-LX3_1)") (class "Default")
      (node (ref "L3") (pin "1") (pinfunction "1_1") (pintype "passive"))
      (node (ref "U4") (pin "31") (pinfunction "LX3_1_31") (pintype "passive"))
      (node (ref "U4") (pin "32") (pinfunction "LX3_2_32") (pintype "passive"))
    )
    (net (code "26") (name "Net-(U4A-LX4_1)") (class "Default")
      (node (ref "L4") (pin "1") (pinfunction "1_1") (pintype "passive"))
      (node (ref "U4") (pin "19") (pinfunction "LX4_1_19") (pintype "passive"))
      (node (ref "U4") (pin "20") (pinfunction "LX4_2_20") (pintype "passive"))
    )
    (net (code "27") (name "Net-(U4A-LX5)") (class "Default")
      (node (ref "L5") (pin "1") (pinfunction "1_1") (pintype "passive"))
      (node (ref "U4") (pin "15") (pinfunction "LX5_15") (pintype "output"))
    )
    (net (code "28") (name "Net-(U4A-LX6_1)") (class "Default")
      (node (ref "L6") (pin "1") (pinfunction "1_1") (pintype "passive"))
      (node (ref "U4") (pin "50") (pinfunction "LX6_1_50") (pintype "passive"))
      (node (ref "U4") (pin "51") (pinfunction "LX6_2_51") (pintype "passive"))
    )
    (net (code "29") (name "Net-(U4A-R_SNSP1)") (class "Default")
      (node (ref "R37") (pin "1") (pinfunction "1_1") (pintype "passive"))
      (node (ref "R38") (pin "1") (pinfunction "1_1") (pintype "passive"))
      (node (ref "U4") (pin "38") (pinfunction "R_SNSP1_38") (pintype "input"))
    )
    (net (code "30") (name "Net-(U4A-R_SNSP2)") (class "Default")
      (node (ref "R35") (pin "1") (pinfunction "1_1") (pintype "passive"))
      (node (ref "R36") (pin "1") (pinfunction "1_1") (pintype "passive"))
      (node (ref "U4") (pin "44") (pinfunction "R_SNSP2_44") (pintype "input"))
    )
    (net (code "31") (name "Net-(U4A-SW_EN)") (class "Default")
      (node (ref "R39") (pin "2") (pinfunction "2_2") (pintype "passive"))
      (node (ref "U4") (pin "12") (pinfunction "SW_EN_12") (pintype "input"))
    )
    (net (code "32") (name "Net-(U4B-LDO2)") (class "Default")
      (node (ref "C110") (pin "1") (pinfunction "1_1") (pintype "passive"))
      (node (ref "TP41") (pin "1") (pinfunction "1_1") (pintype "passive"))
      (node (ref "U4") (pin "2") (pinfunction "LDO2_2") (pintype "passive"))
    )
    (net (code "33") (name "Net-(U4B-LDO4)") (class "Default")
      (node (ref "C115") (pin "1") (pinfunction "1_1") (pintype "passive"))
      (node (ref "TP43") (pin "1") (pinfunction "1_1") (pintype "passive"))
      (node (ref "U4") (pin "1") (pinfunction "LDO4_1") (pintype "passive"))
    )
    (net (code "34") (name "Net-(U4C-CLK_32K_OUT)") (class "Default")
      (node (ref "R49") (pin "1") (pinfunction "1_1") (pintype "passive"))
      (node (ref "U4") (pin "7") (pinfunction "CLK_32K_OUT_7") (pintype "output"))
    )
    (net (code "35") (name "Net-(U4C-PMIC_ON_REQ)") (class "Default")
      (node (ref "R42") (pin "2") (pinfunction "2_2") (pintype "passive"))
      (node (ref "U4") (pin "39") (pinfunction "PMIC_ON_REQ_39") (pintype "input"))
    )
    (net (code "36") (name "Net-(U4C-PMIC_RST_B)") (class "Default")
      (node (ref "R40") (pin "2") (pinfunction "2_2") (pintype "passive"))
      (node (ref "R41") (pin "2") (pinfunction "2_2") (pintype "passive"))
      (node (ref "U4") (pin "8") (pinfunction "PMIC_RST_B_8") (pintype "input"))
    )
    (net (code "37") (name "Net-(U4C-PMIC_STBY_REQ)") (class "Default")
      (node (ref "R43") (pin "2") (pinfunction "2_2") (pintype "passive"))
      (node (ref "U4") (pin "40") (pinfunction "PMIC_STBY_REQ_40") (pintype "input"))
    )
    (net (code "38") (name "Net-(U4C-POR_B)") (class "Default")
      (node (ref "R47") (pin "1") (pinfunction "1_1") (pintype "passive"))
      (node (ref "U4") (pin "9") (pinfunction "POR_B_9") (pintype "output"))
    )
    (net (code "39") (name "Net-(U4C-SCL)") (class "Default")
      (node (ref "R46") (pin "2") (pinfunction "2_2") (pintype "passive"))
      (node (ref "U4") (pin "41") (pinfunction "SCL_41") (pintype "input"))
    )
    (net (code "40") (name "Net-(U4C-SDA)") (class "Default")
      (node (ref "R48") (pin "2") (pinfunction "2_2") (pintype "passive"))
      (node (ref "U4") (pin "42") (pinfunction "SDA_42") (pintype "bidirectional"))
    )
    (net (code "41") (name "Net-(U4C-WDOG_B)") (class "Default")
      (node (ref "R44") (pin "2") (pinfunction "2_2") (pintype "passive"))
      (node (ref "R45") (pin "2") (pinfunction "2_2") (pintype "passive"))
      (node (ref "U4") (pin "28") (pinfunction "WDOG_B_28") (pintype "input"))
    )
    (net (code "42") (name "VDDA_1V8") (class "Default")
      (node (ref "C114") (pin "2") (pinfunction "2_2") (pintype "passive"))
      (node (ref "TP42") (pin "1") (pinfunction "1_1") (pintype "passive"))
      (node (ref "U4") (pin "54") (pinfunction "LDO3_54") (pintype "passive"))
    )
    (net (code "43") (name "VDD_1V8") (class "Default")
      (node (ref "C122") (pin "2") (pinfunction "2_2") (pintype "passive"))
      (node (ref "C123") (pin "2") (pinfunction "2_2") (pintype "passive"))
      (node (ref "L5") (pin "2") (pinfunction "2_2") (pintype "passive"))
      (node (ref "R45") (pin "1") (pinfunction "1_1") (pintype "passive"))
      (node (ref "TP46") (pin "1") (pinfunction "1_1") (pintype "passive"))
      (node (ref "U4") (pin "14") (pinfunction "BUCK5FB_14") (pintype "input"))
    )
    (net (code "44") (name "VDD_3V3") (class "Default")
      (node (ref "C116") (pin "2") (pinfunction "2_2") (pintype "passive"))
      (node (ref "C117") (pin "2") (pinfunction "2_2") (pintype "passive"))
      (node (ref "C127") (pin "2") (pinfunction "2_2") (pintype "passive"))
      (node (ref "L4") (pin "2") (pinfunction "2_2") (pintype "passive"))
      (node (ref "TP44") (pin "1") (pinfunction "1_1") (pintype "passive"))
      (node (ref "U4") (pin "21") (pinfunction "BUCK4FB_21") (pintype "input"))
      (node (ref "U4") (pin "22") (pinfunction "SWIN_22") (pintype "input"))
    )
    (net (code "45") (name "VDD_ARM") (class "Default")
      (node (ref "C103") (pin "2") (pinfunction "2_2") (pintype "passive"))
      (node (ref "C104") (pin "2") (pinfunction "2_2") (pintype "passive"))
      (node (ref "L1") (pin "2") (pinfunction "2_2") (pintype "passive"))
      (node (ref "R35") (pin "2") (pinfunction "2_2") (pintype "passive"))
      (node (ref "TP38") (pin "1") (pinfunction "1_1") (pintype "passive"))
    )
    (net (code "46") (name "VDD_ARM_S") (class "Default")
      (node (ref "R36") (pin "2") (pinfunction "2_2") (pintype "passive"))
    )
    (net (code "47") (name "VDD_SOC") (class "Default")
      (node (ref "C107") (pin "2") (pinfunction "2_2") (pintype "passive"))
      (node (ref "C108") (pin "2") (pinfunction "2_2") (pintype "passive"))
      (node (ref "C112") (pin "2") (pinfunction "2_2") (pintype "passive"))
      (node (ref "C113") (pin "2") (pinfunction "2_2") (pintype "passive"))
      (node (ref "L2") (pin "2") (pinfunction "2_2") (pintype "passive"))
      (node (ref "L3") (pin "2") (pinfunction "2_2") (pintype "passive"))
      (node (ref "R37") (pin "2") (pinfunction "2_2") (pintype "passive"))
      (node (ref "TP40") (pin "1") (pinfunction "1_1") (pintype "passive"))
    )
    (net (code "48") (name "VDD_SOC_S") (class "Default")
      (node (ref "R38") (pin "2") (pinfunction "2_2") (pintype "passive"))
    )
    (net (code "49") (name "VSD_3V3") (class "Default")
      (node (ref "C128") (pin "2") (pinfunction "2_2") (pintype "passive"))
      (node (ref "U4") (pin "23") (pinfunction "SWOUT_23") (pintype "output"))
    )
    (net (code "50") (name "VSYS_5V") (class "Default")
      (node (ref "C102") (pin "2") (pinfunction "2_2") (pintype "passive"))
      (node (ref "C105") (pin "2") (pinfunction "2_2") (pintype "passive"))
      (node (ref "C109") (pin "2") (pinfunction "2_2") (pintype "passive"))
      (node (ref "C111") (pin "2") (pinfunction "2_2") (pintype "passive"))
      (node (ref "C118") (pin "2") (pinfunction "2_2") (pintype "passive"))
      (node (ref "C119") (pin "2") (pinfunction "2_2") (pintype "passive"))
      (node (ref "C121") (pin "2") (pinfunction "2_2") (pintype "passive"))
      (node (ref "C126") (pin "2") (pinfunction "2_2") (pintype "passive"))
      (node (ref "C129") (pin "2") (pinfunction "2_2") (pintype "passive"))
      (node (ref "TP49") (pin "1") (pinfunction "1_1") (pintype "passive"))
      (node (ref "U4") (pin "16") (pinfunction "INB45_1_16") (pintype "input"))
      (node (ref "U4") (pin "17") (pinfunction "INB45_2_17") (pintype "input"))
      (node (ref "U4") (pin "18") (pinfunction "INB45_3_18") (pintype "input"))
      (node (ref "U4") (pin "33") (pinfunction "INB13_1_33") (pintype "input"))
      (node (ref "U4") (pin "34") (pinfunction "INB13_2_34") (pintype "input"))
      (node (ref "U4") (pin "35") (pinfunction "INB13_3_35") (pintype "input"))
      (node (ref "U4") (pin "47") (pinfunction "INB26_1_47") (pintype "input"))
      (node (ref "U4") (pin "48") (pinfunction "INB26_2_48") (pintype "input"))
      (node (ref "U4") (pin "49") (pinfunction "INB26_3_49") (pintype "input"))
      (node (ref "U4") (pin "53") (pinfunction "VSYS_53") (pintype "power_in"))
      (node (ref "U4") (pin "56") (pinfunction "INL1_56") (pintype "input"))
    )
    (net (code "51") (name "unconnected-(U4C-RTC_RESET_B-Pad6)") (class "Default")
      (node (ref "U4") (pin "6") (pinfunction "RTC_RESET_B_6") (pintype "open_collector+no_connect"))
    )
  )
)
